# 01_MCU.net
KiCad netlist of a schematic drawn in Altium Designer
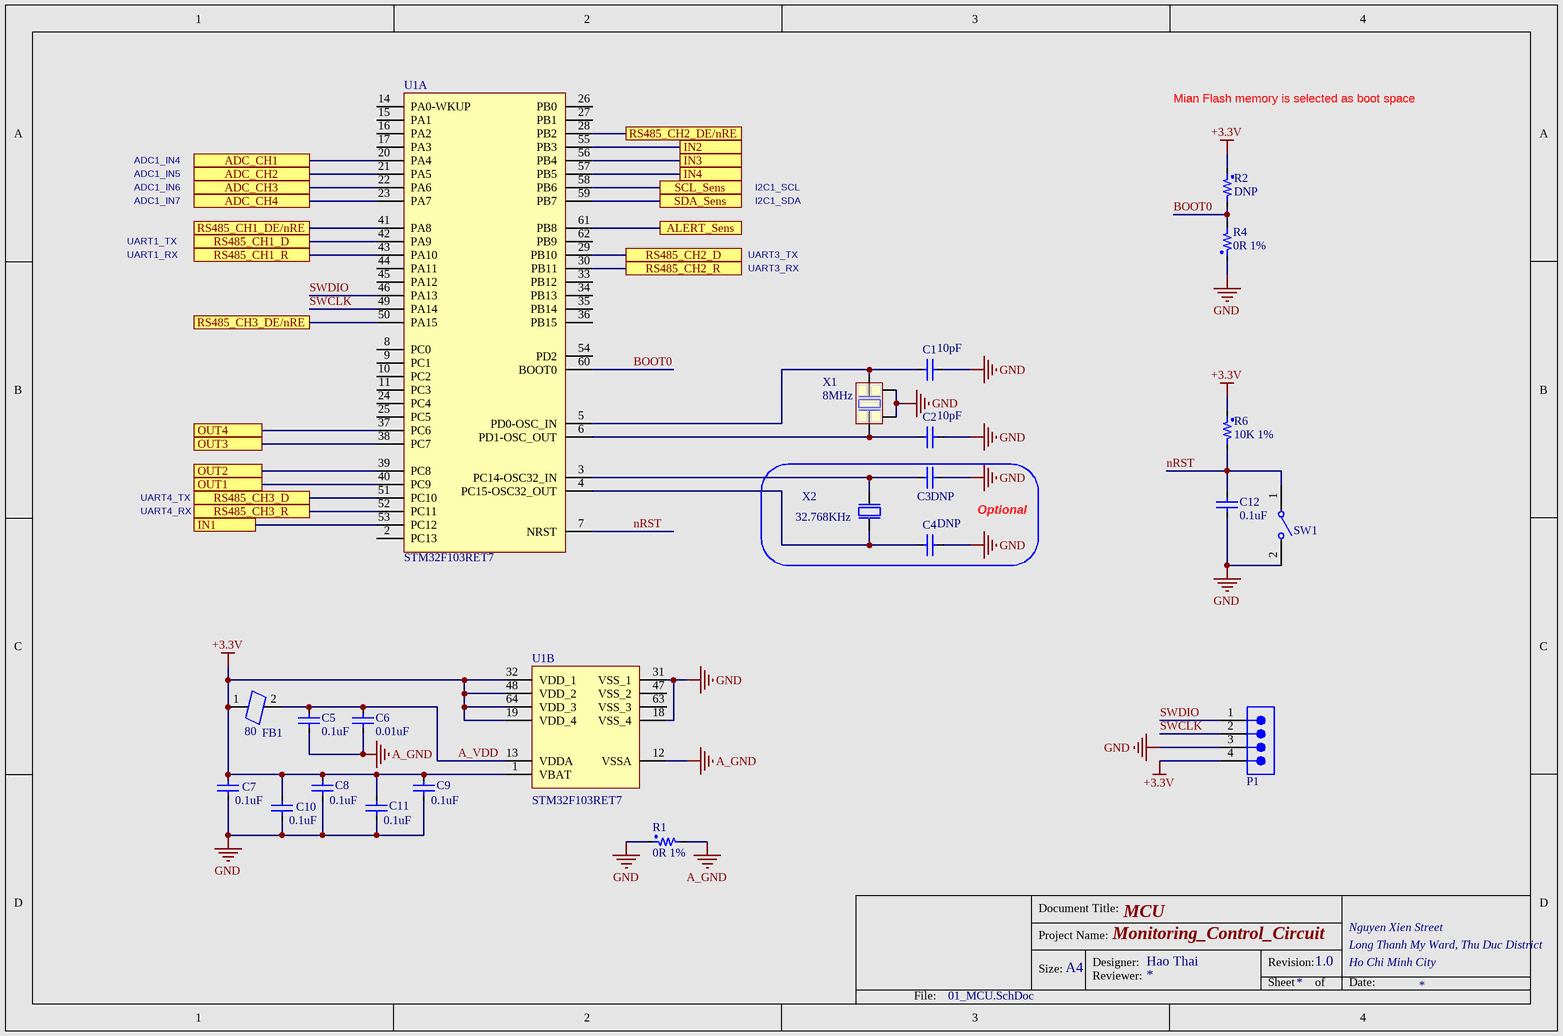
[diagram p0: 01_MCU.SchDoc]

(export (version "E")
  (design (tool "Eeschema 10.0.6"))
  (components
    (comp (ref "C1")
      (value "10pF")
      (footprint "Capacitor:C0603 (1608 metric)")
      (description "Multilayer Ceramic Capacitors MLCC - SMD/SMT 10pF 250V C0G +/-5% 0603")
      (fields (field (name "MFR PART NUMBER") "CC0603JRNPO9BN100") (field (name "MFR") "Yageo"))
      (libsource (lib "CeramicCapacitor") (part "CC0603JRNPO9BN100"))
    )
    (comp (ref "C2")
      (value "10pF")
      (footprint "Capacitor:C0603 (1608 metric)")
      (description "Multilayer Ceramic Capacitors MLCC - SMD/SMT 10pF 250V C0G +/-5% 0603")
      (fields (field (name "MFR PART NUMBER") "CC0603JRNPO9BN100") (field (name "MFR") "Yageo"))
      (libsource (lib "CeramicCapacitor") (part "CC0603JRNPO9BN100"))
    )
    (comp (ref "C3")
      (value "DNP")
      (footprint "Capacitor:C0603 (1608 metric)")
      (description "Multilayer Ceramic Capacitors MLCC - SMD/SMT 12pF 250V C0G +/-5% 0603")
      (fields (field (name "MFR PART NUMBER") "CC0603JRNPO9BN120") (field (name "MFR") "Yageo"))
      (libsource (lib "CeramicCapacitor") (part "CC0603JRNPO9BN120"))
    )
    (comp (ref "C4")
      (value "DNP")
      (footprint "Capacitor:C0603 (1608 metric)")
      (description "Multilayer Ceramic Capacitors MLCC - SMD/SMT 12pF 250V C0G +/-5% 0603")
      (fields (field (name "MFR PART NUMBER") "CC0603JRNPO9BN120") (field (name "MFR") "Yageo"))
      (libsource (lib "CeramicCapacitor") (part "CC0603JRNPO9BN120"))
    )
    (comp (ref "C5")
      (value "0.1uF")
      (footprint "Capacitor:C0603 (1608 metric)")
      (description "Multilayer Ceramic Capacitors MLCC - SMD/SMT 0.1uF 50V X7R +/-10% 0603")
      (fields (field (name "MFR PART NUMBER") "CC0603KRX7R9BB104") (field (name "MFR") "Yageo"))
      (libsource (lib "CeramicCapacitor") (part "CC0603KRX7R9BB104"))
    )
    (comp (ref "C6")
      (value "0.01uF")
      (footprint "Capacitor:C0603 (1608 metric)")
      (description "Multilayer Ceramic Capacitors MLCC - SMD/SMT 0.01uF 50V X7R +/-10% 0603")
      (fields (field (name "MFR PART NUMBER") "CC0603KRX7R9BB103") (field (name "MFR") "Yageo"))
      (libsource (lib "CeramicCapacitor") (part "CC0603KRX7R9BB103"))
    )
    (comp (ref "C7")
      (value "0.1uF")
      (footprint "Capacitor:C0603 (1608 metric)")
      (description "Multilayer Ceramic Capacitors MLCC - SMD/SMT 0.1uF 50V X7R +/-10% 0603")
      (fields (field (name "MFR PART NUMBER") "CC0603KRX7R9BB104") (field (name "MFR") "Yageo"))
      (libsource (lib "CeramicCapacitor") (part "CC0603KRX7R9BB104"))
    )
    (comp (ref "C8")
      (value "0.1uF")
      (footprint "Capacitor:C0603 (1608 metric)")
      (description "Multilayer Ceramic Capacitors MLCC - SMD/SMT 0.1uF 50V X7R +/-10% 0603")
      (fields (field (name "MFR PART NUMBER") "CC0603KRX7R9BB104") (field (name "MFR") "Yageo"))
      (libsource (lib "CeramicCapacitor") (part "CC0603KRX7R9BB104"))
    )
    (comp (ref "C9")
      (value "0.1uF")
      (footprint "Capacitor:C0603 (1608 metric)")
      (description "Multilayer Ceramic Capacitors MLCC - SMD/SMT 0.1uF 50V X7R +/-10% 0603")
      (fields (field (name "MFR PART NUMBER") "CC0603KRX7R9BB104") (field (name "MFR") "Yageo"))
      (libsource (lib "CeramicCapacitor") (part "CC0603KRX7R9BB104"))
    )
    (comp (ref "C10")
      (value "0.1uF")
      (footprint "Capacitor:C0603 (1608 metric)")
      (description "Multilayer Ceramic Capacitors MLCC - SMD/SMT 0.1uF 50V X7R +/-10% 0603")
      (fields (field (name "MFR PART NUMBER") "CC0603KRX7R9BB104") (field (name "MFR") "Yageo"))
      (libsource (lib "CeramicCapacitor") (part "CC0603KRX7R9BB104"))
    )
    (comp (ref "C11")
      (value "0.1uF")
      (footprint "Capacitor:C0603 (1608 metric)")
      (description "Multilayer Ceramic Capacitors MLCC - SMD/SMT 0.1uF 50V X7R +/-10% 0603")
      (fields (field (name "MFR PART NUMBER") "CC0603KRX7R9BB104") (field (name "MFR") "Yageo"))
      (libsource (lib "CeramicCapacitor") (part "CC0603KRX7R9BB104"))
    )
    (comp (ref "C12")
      (value "0.1uF")
      (footprint "Capacitor:C0603 (1608 metric)")
      (description "Multilayer Ceramic Capacitors MLCC - SMD/SMT 0.1uF 50V X7R +/-10% 0603")
      (fields (field (name "MFR PART NUMBER") "CC0603KRX7R9BB104") (field (name "MFR") "Yageo"))
      (libsource (lib "CeramicCapacitor") (part "CC0603KRX7R9BB104"))
    )
    (comp (ref "FB1")
      (value "80")
      (footprint "Inductor:FB0805 (2012 METRIC)")
      (description "Ferrite Beads HI CUR CHIP BD 0805 80OHMS 25%")
      (fields (field (name "MFR PART NUMBER") "FBMH2012HM800-T") (field (name "MFR") "Taiyo Yuden"))
      (libsource (lib "FerriteBead") (part "FBMH2012HM800-T"))
    )
    (comp (ref "P1")
      (value "61300411121")
      (footprint "61300411121")
      (description "WR-PHD Pin Header, THT, Vertical, pitch 2.54mm, 1 Row, 4P")
      (fields (field (name "MFR") "Wurth Elektronik"))
      (libsource (lib "Altium_WR-PHD (rev22b)") (part "61300411121"))
    )
    (comp (ref "R1")
      (value "0R 1%")
      (footprint "Resistor:R0603 (1608 Metric)")
      (description "Thick Film Resistors - SMD 0 OHM 1% Case 0603")
      (fields (field (name "MFR PART NUMBER") "RC0603FR-070RL") (field (name "MFR") "Yageo"))
      (libsource (lib "ChipResistor") (part "RC0603FR-070RL"))
    )
    (comp (ref "R2")
      (value "DNP")
      (footprint "Resistor:R0603 (1608 Metric)")
      (description "Thick Film Resistors - SMD 10K OHM 1% Case 0603")
      (fields (field (name "MFR PART NUMBER") "RC0603FR-0710KL") (field (name "MFR") "Yageo"))
      (libsource (lib "ChipResistor") (part "RC0603FR-0710KL"))
    )
    (comp (ref "R4")
      (value "0R 1%")
      (footprint "Resistor:R0603 (1608 Metric)")
      (description "Thick Film Resistors - SMD 0 OHM 1% Case 0603")
      (fields (field (name "MFR PART NUMBER") "RC0603FR-070RL") (field (name "MFR") "Yageo"))
      (libsource (lib "ChipResistor") (part "RC0603FR-070RL"))
    )
    (comp (ref "R6")
      (value "10K 1%")
      (footprint "Resistor:R0603 (1608 Metric)")
      (description "Thick Film Resistors - SMD 10K OHM 1% Case 0603")
      (fields (field (name "MFR PART NUMBER") "RC0603FR-0710KL") (field (name "MFR") "Yageo"))
      (libsource (lib "ChipResistor") (part "RC0603FR-0710KL"))
    )
    (comp (ref "SW1")
      (value "434121025816")
      (footprint "WS-TASV_L6W3.8H2.5_4341x10258x6")
      (description "WS-TASV SMT Tact Switch, SPST-NO, 12VDC, 50mA, 160g")
      (fields (field (name "MFR") "Wurth Elektronik"))
      (libsource (lib "Altium_WS-TASV (rev22b)") (part "434121025816"))
    )
    (comp (ref "U1")
      (value "STM32F103RET7")
      (footprint "STM-LQFP64_N")
      (fields (field (name "MFR") "STMicroelectronics"))
      (libsource (lib "MCU") (part "STM32F103RET7"))
    )
    (comp (ref "X1")
      (value "8MHz")
      (footprint "Crystal:TSX_3225")
      (fields
        (field (name "MFR") "ECS")
        (field (name "MFR PART NUMBER") "ECS-80-10-33-CHN-TR")
        (field (name "TOLERANCE") "10 PPM")
      )
      (libsource (lib "Crystal") (part "ECS-80-10-33-CHN-TR"))
    )
    (comp (ref "X2")
      (value "32.768KHz")
      (footprint "Crystal:XTAL_3215_2Pin")
      (description "Crystals 32.768KHz 20ppm 12.5pF -40C +85C")
      (fields (field (name "MFR PART NUMBER") "ECS-.327-12.5-34B-TR") (field (name "MFR") "ECS"))
      (libsource (lib "Crystal") (part "ECS-.327-12.5-34B-TR"))
    )
  )
  (nets
    (net (code "1") (name "+3.3V") (class "Default")
      (node (ref "C10") (pin "2") (pinfunction "2_2") (pintype "passive"))
      (node (ref "C11") (pin "2") (pinfunction "2_2") (pintype "passive"))
      (node (ref "C7") (pin "2") (pinfunction "2_2") (pintype "passive"))
      (node (ref "C8") (pin "2") (pinfunction "2_2") (pintype "passive"))
      (node (ref "C9") (pin "2") (pinfunction "2_2") (pintype "passive"))
      (node (ref "FB1") (pin "1") (pinfunction "1_1") (pintype "passive"))
      (node (ref "P1") (pin "4") (pinfunction "4_4") (pintype "passive"))
      (node (ref "R2") (pin "1") (pinfunction "1_1") (pintype "passive"))
      (node (ref "R6") (pin "1") (pinfunction "1_1") (pintype "passive"))
      (node (ref "U1") (pin "1") (pinfunction "VBAT_1") (pintype "power_in"))
      (node (ref "U1") (pin "19") (pinfunction "VDD_4_19") (pintype "power_in"))
      (node (ref "U1") (pin "32") (pinfunction "VDD_1_32") (pintype "power_in"))
      (node (ref "U1") (pin "48") (pinfunction "VDD_2_48") (pintype "power_in"))
      (node (ref "U1") (pin "64") (pinfunction "VDD_3_64") (pintype "power_in"))
    )
    (net (code "2") (name "/ADC_CH1") (class "Default")
      (node (ref "U1") (pin "20") (pinfunction "PA4_20") (pintype "passive"))
    )
    (net (code "3") (name "/ADC_CH2") (class "Default")
      (node (ref "U1") (pin "21") (pinfunction "PA5_21") (pintype "passive"))
    )
    (net (code "4") (name "/ADC_CH3") (class "Default")
      (node (ref "U1") (pin "22") (pinfunction "PA6_22") (pintype "passive"))
    )
    (net (code "5") (name "/ADC_CH4") (class "Default")
      (node (ref "U1") (pin "23") (pinfunction "PA7_23") (pintype "passive"))
    )
    (net (code "6") (name "/ALERT_Sens") (class "Default")
      (node (ref "U1") (pin "61") (pinfunction "PB8_61") (pintype "passive"))
    )
    (net (code "7") (name "/A_VDD") (class "Default")
      (node (ref "C5") (pin "2") (pinfunction "2_2") (pintype "passive"))
      (node (ref "C6") (pin "2") (pinfunction "2_2") (pintype "passive"))
      (node (ref "FB1") (pin "2") (pinfunction "2_2") (pintype "passive"))
      (node (ref "U1") (pin "13") (pinfunction "VDDA_13") (pintype "power_in"))
    )
    (net (code "8") (name "/BOOT0") (class "Default")
      (node (ref "R2") (pin "2") (pinfunction "2_2") (pintype "passive"))
      (node (ref "R4") (pin "2") (pinfunction "2_2") (pintype "passive"))
      (node (ref "U1") (pin "60") (pinfunction "BOOT0_60") (pintype "passive"))
    )
    (net (code "9") (name "/IN1") (class "Default")
      (node (ref "U1") (pin "53") (pinfunction "PC12_53") (pintype "passive"))
    )
    (net (code "10") (name "/IN2") (class "Default")
      (node (ref "U1") (pin "55") (pinfunction "PB3_55") (pintype "passive"))
    )
    (net (code "11") (name "/IN3") (class "Default")
      (node (ref "U1") (pin "56") (pinfunction "PB4_56") (pintype "passive"))
    )
    (net (code "12") (name "/IN4") (class "Default")
      (node (ref "U1") (pin "57") (pinfunction "PB5_57") (pintype "passive"))
    )
    (net (code "13") (name "/OUT1") (class "Default")
      (node (ref "U1") (pin "40") (pinfunction "PC9_40") (pintype "passive"))
    )
    (net (code "14") (name "/OUT2") (class "Default")
      (node (ref "U1") (pin "39") (pinfunction "PC8_39") (pintype "passive"))
    )
    (net (code "15") (name "/OUT3") (class "Default")
      (node (ref "U1") (pin "38") (pinfunction "PC7_38") (pintype "passive"))
    )
    (net (code "16") (name "/OUT4") (class "Default")
      (node (ref "U1") (pin "37") (pinfunction "PC6_37") (pintype "passive"))
    )
    (net (code "17") (name "/RS485_CH1_D") (class "Default")
      (node (ref "U1") (pin "42") (pinfunction "PA9_42") (pintype "passive"))
    )
    (net (code "18") (name "/RS485_CH1_DE{slash}nRE") (class "Default")
      (node (ref "U1") (pin "41") (pinfunction "PA8_41") (pintype "passive"))
    )
    (net (code "19") (name "/RS485_CH1_R") (class "Default")
      (node (ref "U1") (pin "43") (pinfunction "PA10_43") (pintype "passive"))
    )
    (net (code "20") (name "/RS485_CH2_D") (class "Default")
      (node (ref "U1") (pin "29") (pinfunction "PB10_29") (pintype "passive"))
    )
    (net (code "21") (name "/RS485_CH2_DE{slash}nRE") (class "Default")
      (node (ref "U1") (pin "28") (pinfunction "PB2_28") (pintype "passive"))
    )
    (net (code "22") (name "/RS485_CH2_R") (class "Default")
      (node (ref "U1") (pin "30") (pinfunction "PB11_30") (pintype "passive"))
    )
    (net (code "23") (name "/RS485_CH3_D") (class "Default")
      (node (ref "U1") (pin "51") (pinfunction "PC10_51") (pintype "passive"))
    )
    (net (code "24") (name "/RS485_CH3_DE{slash}nRE") (class "Default")
      (node (ref "U1") (pin "50") (pinfunction "PA15_50") (pintype "passive"))
    )
    (net (code "25") (name "/RS485_CH3_R") (class "Default")
      (node (ref "U1") (pin "52") (pinfunction "PC11_52") (pintype "passive"))
    )
    (net (code "26") (name "/SCL_Sens") (class "Default")
      (node (ref "U1") (pin "58") (pinfunction "PB6_58") (pintype "passive"))
    )
    (net (code "27") (name "/SDA_Sens") (class "Default")
      (node (ref "U1") (pin "59") (pinfunction "PB7_59") (pintype "passive"))
    )
    (net (code "28") (name "/SWCLK") (class "Default")
      (node (ref "P1") (pin "2") (pinfunction "2_2") (pintype "passive"))
      (node (ref "U1") (pin "49") (pinfunction "PA14_49") (pintype "passive"))
    )
    (net (code "29") (name "/SWDIO") (class "Default")
      (node (ref "P1") (pin "1") (pinfunction "1_1") (pintype "passive"))
      (node (ref "U1") (pin "46") (pinfunction "PA13_46") (pintype "passive"))
    )
    (net (code "30") (name "/nRST") (class "Default")
      (node (ref "C12") (pin "1") (pinfunction "1_1") (pintype "passive"))
      (node (ref "R6") (pin "2") (pinfunction "2_2") (pintype "passive"))
      (node (ref "SW1") (pin "1") (pinfunction "1_1") (pintype "passive"))
      (node (ref "U1") (pin "7") (pinfunction "NRST_7") (pintype "passive"))
    )
    (net (code "31") (name "A_GND") (class "Default")
      (node (ref "C5") (pin "1") (pinfunction "1_1") (pintype "passive"))
      (node (ref "C6") (pin "1") (pinfunction "1_1") (pintype "passive"))
      (node (ref "R1") (pin "2") (pinfunction "2_2") (pintype "passive"))
      (node (ref "U1") (pin "12") (pinfunction "VSSA_12") (pintype "power_in"))
    )
    (net (code "32") (name "GND") (class "Default")
      (node (ref "C1") (pin "1") (pinfunction "1_1") (pintype "passive"))
      (node (ref "C10") (pin "1") (pinfunction "1_1") (pintype "passive"))
      (node (ref "C11") (pin "1") (pinfunction "1_1") (pintype "passive"))
      (node (ref "C12") (pin "2") (pinfunction "2_2") (pintype "passive"))
      (node (ref "C2") (pin "1") (pinfunction "1_1") (pintype "passive"))
      (node (ref "C3") (pin "2") (pinfunction "2_2") (pintype "passive"))
      (node (ref "C4") (pin "2") (pinfunction "2_2") (pintype "passive"))
      (node (ref "C7") (pin "1") (pinfunction "1_1") (pintype "passive"))
      (node (ref "C8") (pin "1") (pinfunction "1_1") (pintype "passive"))
      (node (ref "C9") (pin "1") (pinfunction "1_1") (pintype "passive"))
      (node (ref "P1") (pin "3") (pinfunction "3_3") (pintype "passive"))
      (node (ref "R1") (pin "1") (pinfunction "1_1") (pintype "passive"))
      (node (ref "R4") (pin "1") (pinfunction "1_1") (pintype "passive"))
      (node (ref "SW1") (pin "2") (pinfunction "2_2") (pintype "passive"))
      (node (ref "U1") (pin "18") (pinfunction "VSS_4_18") (pintype "power_in"))
      (node (ref "U1") (pin "31") (pinfunction "VSS_1_31") (pintype "power_in"))
      (node (ref "X1") (pin "2") (pinfunction "GND_2") (pintype "passive"))
      (node (ref "X1") (pin "4") (pinfunction "GND_4") (pintype "passive"))
    )
    (net (code "33") (name "Net-(U1A-PC14-OSC32_IN)") (class "Default")
      (node (ref "C3") (pin "1") (pinfunction "1_1") (pintype "passive"))
      (node (ref "U1") (pin "3") (pinfunction "PC14-OSC32_IN_3") (pintype "passive"))
      (node (ref "X2") (pin "2") (pinfunction "out_2") (pintype "passive"))
    )
    (net (code "34") (name "Net-(U1A-PC15-OSC32_OUT)") (class "Default")
      (node (ref "C4") (pin "1") (pinfunction "1_1") (pintype "passive"))
      (node (ref "U1") (pin "4") (pinfunction "PC15-OSC32_OUT_4") (pintype "passive"))
      (node (ref "X2") (pin "1") (pinfunction "inp_1") (pintype "passive"))
    )
    (net (code "35") (name "Net-(U1A-PD0-OSC_IN)") (class "Default")
      (node (ref "C1") (pin "2") (pinfunction "2_2") (pintype "passive"))
      (node (ref "U1") (pin "5") (pinfunction "PD0-OSC_IN_5") (pintype "passive"))
      (node (ref "X1") (pin "1") (pinfunction "Input_1") (pintype "passive"))
    )
    (net (code "36") (name "Net-(U1A-PD1-OSC_OUT)") (class "Default")
      (node (ref "C2") (pin "2") (pinfunction "2_2") (pintype "passive"))
      (node (ref "U1") (pin "6") (pinfunction "PD1-OSC_OUT_6") (pintype "passive"))
      (node (ref "X1") (pin "3") (pinfunction "Out_3") (pintype "passive"))
    )
    (net (code "37") (name "unconnected-(U1A-PA0-WKUP-Pad14)") (class "Default")
      (node (ref "U1") (pin "14") (pinfunction "PA0-WKUP_14") (pintype "passive"))
    )
    (net (code "38") (name "unconnected-(U1A-PA1-Pad15)") (class "Default")
      (node (ref "U1") (pin "15") (pinfunction "PA1_15") (pintype "passive"))
    )
    (net (code "39") (name "unconnected-(U1A-PA2-Pad16)") (class "Default")
      (node (ref "U1") (pin "16") (pinfunction "PA2_16") (pintype "passive"))
    )
    (net (code "40") (name "unconnected-(U1A-PA3-Pad17)") (class "Default")
      (node (ref "U1") (pin "17") (pinfunction "PA3_17") (pintype "passive"))
    )
    (net (code "41") (name "unconnected-(U1A-PA11-Pad44)") (class "Default")
      (node (ref "U1") (pin "44") (pinfunction "PA11_44") (pintype "passive"))
    )
    (net (code "42") (name "unconnected-(U1A-PA12-Pad45)") (class "Default")
      (node (ref "U1") (pin "45") (pinfunction "PA12_45") (pintype "passive"))
    )
    (net (code "43") (name "unconnected-(U1A-PB0-Pad26)") (class "Default")
      (node (ref "U1") (pin "26") (pinfunction "PB0_26") (pintype "passive"))
    )
    (net (code "44") (name "unconnected-(U1A-PB1-Pad27)") (class "Default")
      (node (ref "U1") (pin "27") (pinfunction "PB1_27") (pintype "passive"))
    )
    (net (code "45") (name "unconnected-(U1A-PB9-Pad62)") (class "Default")
      (node (ref "U1") (pin "62") (pinfunction "PB9_62") (pintype "passive"))
    )
    (net (code "46") (name "unconnected-(U1A-PB12-Pad33)") (class "Default")
      (node (ref "U1") (pin "33") (pinfunction "PB12_33") (pintype "passive"))
    )
    (net (code "47") (name "unconnected-(U1A-PB13-Pad34)") (class "Default")
      (node (ref "U1") (pin "34") (pinfunction "PB13_34") (pintype "passive"))
    )
    (net (code "48") (name "unconnected-(U1A-PB14-Pad35)") (class "Default")
      (node (ref "U1") (pin "35") (pinfunction "PB14_35") (pintype "passive"))
    )
    (net (code "49") (name "unconnected-(U1A-PB15-Pad36)") (class "Default")
      (node (ref "U1") (pin "36") (pinfunction "PB15_36") (pintype "passive"))
    )
    (net (code "50") (name "unconnected-(U1A-PC0-Pad8)") (class "Default")
      (node (ref "U1") (pin "8") (pinfunction "PC0_8") (pintype "passive"))
    )
    (net (code "51") (name "unconnected-(U1A-PC1-Pad9)") (class "Default")
      (node (ref "U1") (pin "9") (pinfunction "PC1_9") (pintype "passive"))
    )
    (net (code "52") (name "unconnected-(U1A-PC2-Pad10)") (class "Default")
      (node (ref "U1") (pin "10") (pinfunction "PC2_10") (pintype "passive"))
    )
    (net (code "53") (name "unconnected-(U1A-PC3-Pad11)") (class "Default")
      (node (ref "U1") (pin "11") (pinfunction "PC3_11") (pintype "passive"))
    )
    (net (code "54") (name "unconnected-(U1A-PC4-Pad24)") (class "Default")
      (node (ref "U1") (pin "24") (pinfunction "PC4_24") (pintype "passive"))
    )
    (net (code "55") (name "unconnected-(U1A-PC5-Pad25)") (class "Default")
      (node (ref "U1") (pin "25") (pinfunction "PC5_25") (pintype "passive"))
    )
    (net (code "56") (name "unconnected-(U1A-PC13-Pad2)") (class "Default")
      (node (ref "U1") (pin "2") (pinfunction "PC13_2") (pintype "passive"))
    )
    (net (code "57") (name "unconnected-(U1A-PD2-Pad54)") (class "Default")
      (node (ref "U1") (pin "54") (pinfunction "PD2_54") (pintype "passive"))
    )
    (net (code "58") (name "unconnected-(U1B-VSS_2-Pad47)") (class "Default")
      (node (ref "U1") (pin "47") (pinfunction "VSS_2_47") (pintype "power_in"))
    )
    (net (code "59") (name "unconnected-(U1B-VSS_3-Pad63)") (class "Default")
      (node (ref "U1") (pin "63") (pinfunction "VSS_3_63") (pintype "power_in"))
    )
  )
)
